# Game_Consol_Top.net
KiCad netlist of a schematic drawn in Altium Designer
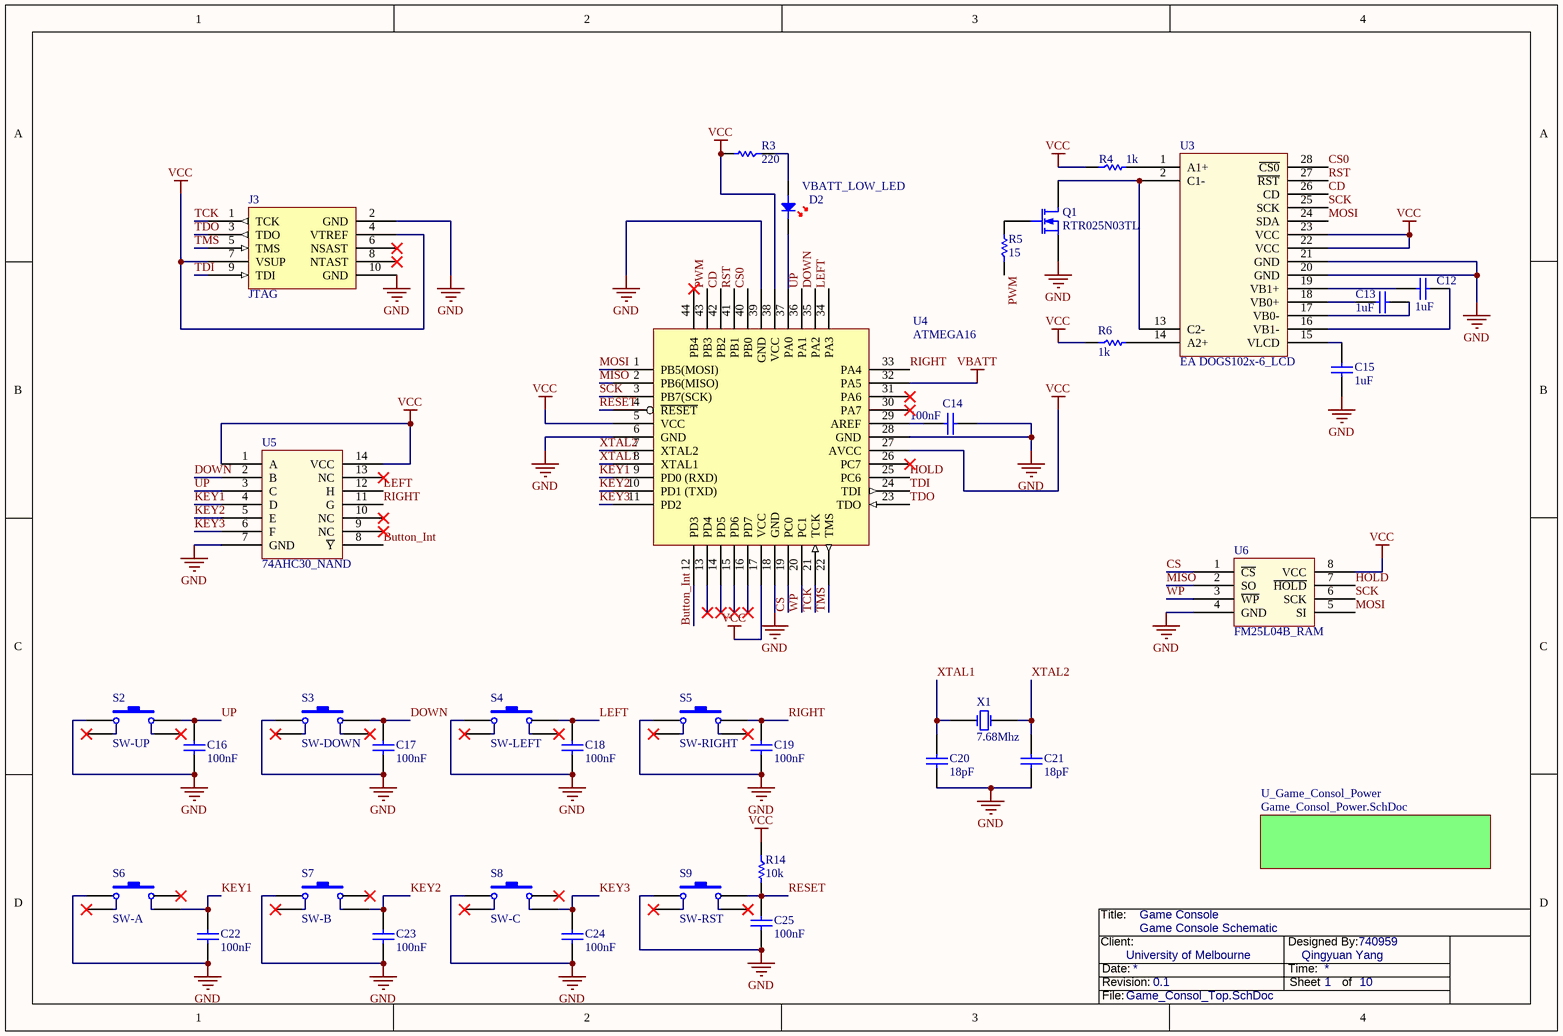
[diagram p0: Game_Consol_Top.SchDoc]

(export (version "E")
  (design (tool "Eeschema 10.0.6"))
  (components
    (comp (ref "C12")
      (value "1uF")
      (footprint "0805")
      (description "Capacitor 100nF")
      (libsource (lib "EmbSD Lib 0v1") (part "C 0805"))
    )
    (comp (ref "C13")
      (value "1uF")
      (footprint "0805")
      (description "Capacitor 100nF")
      (libsource (lib "EmbSD Lib 0v1") (part "C 0805"))
    )
    (comp (ref "C14")
      (value "100nF")
      (footprint "0805")
      (description "Capacitor 100nF")
      (libsource (lib "EmbSD Lib 0v1") (part "C 0805"))
    )
    (comp (ref "C15")
      (value "1uF")
      (footprint "0805")
      (description "Capacitor 100nF")
      (libsource (lib "EmbSD Lib 0v1") (part "C 0805"))
    )
    (comp (ref "C16")
      (value "100nF")
      (footprint "0805")
      (description "Capacitor 100nF")
      (libsource (lib "EmbSD Lib 0v1") (part "C 0805"))
    )
    (comp (ref "C17")
      (value "100nF")
      (footprint "0805")
      (description "Capacitor 100nF")
      (libsource (lib "EmbSD Lib 0v1") (part "C 0805"))
    )
    (comp (ref "C18")
      (value "100nF")
      (footprint "0805")
      (description "Capacitor 100nF")
      (libsource (lib "EmbSD Lib 0v1") (part "C 0805"))
    )
    (comp (ref "C19")
      (value "100nF")
      (footprint "0805")
      (description "Capacitor 100nF")
      (libsource (lib "EmbSD Lib 0v1") (part "C 0805"))
    )
    (comp (ref "C20")
      (value "18pF")
      (footprint "0805")
      (description "Capacitor 100nF")
      (libsource (lib "EmbSD Lib 0v1") (part "C 0805"))
    )
    (comp (ref "C21")
      (value "18pF")
      (footprint "0805")
      (description "Capacitor 100nF")
      (libsource (lib "EmbSD Lib 0v1") (part "C 0805"))
    )
    (comp (ref "C22")
      (value "100nF")
      (footprint "0805")
      (description "Capacitor 100nF")
      (libsource (lib "EmbSD Lib 0v1") (part "C 0805"))
    )
    (comp (ref "C23")
      (value "100nF")
      (footprint "0805")
      (description "Capacitor 100nF")
      (libsource (lib "EmbSD Lib 0v1") (part "C 0805"))
    )
    (comp (ref "C24")
      (value "100nF")
      (footprint "0805")
      (description "Capacitor 100nF")
      (libsource (lib "EmbSD Lib 0v1") (part "C 0805"))
    )
    (comp (ref "C25")
      (value "100nF")
      (footprint "0805")
      (description "Capacitor 100nF")
      (libsource (lib "EmbSD Lib 0v1") (part "C 0805"))
    )
    (comp (ref "D2")
      (value "VBATT_LOW_LED")
      (footprint "0805D")
      (description "Light Emitting Diode")
      (fields (field (name "MANUFACTURER") "Generic Components") (field (name "PUBLISHER") "Altium Limited"))
      (libsource (lib "EmbSD Lib 0v1") (part "LED RED"))
    )
    (comp (ref "J3")
      (value "JTAG")
      (footprint "BOXEDVERT10")
      (description "JTAG ATMEL connector")
      (libsource (lib "EmbSD Lib 0v1") (part "JTAG_CON"))
    )
    (comp (ref "Q1")
      (value "RTR025N03TL")
      (footprint "SOT23")
      (description "N-Channel MOSFET")
      (fields (field (name "PUBLISHER") "Altium Limited"))
      (libsource (lib "EmbSD Lib 0v1") (part "MOSFET-N"))
    )
    (comp (ref "R3")
      (value "220")
      (footprint "0805")
      (description "Resistor")
      (libsource (lib "EmbSD Lib 0v1") (part "R"))
    )
    (comp (ref "R4")
      (value "1k")
      (footprint "0805")
      (description "Resistor")
      (libsource (lib "EmbSD Lib 0v1") (part "R"))
    )
    (comp (ref "R5")
      (value "15")
      (footprint "0805")
      (description "Resistor")
      (libsource (lib "EmbSD Lib 0v1") (part "R"))
    )
    (comp (ref "R6")
      (value "1k")
      (footprint "0805")
      (description "Resistor")
      (libsource (lib "EmbSD Lib 0v1") (part "R"))
    )
    (comp (ref "R14")
      (value "10k")
      (footprint "0805")
      (description "Resistor")
      (libsource (lib "EmbSD Lib 0v1") (part "R"))
    )
    (comp (ref "S2")
      (value "SW-UP")
      (footprint "SPNO_SMD")
      (description "Push Button Switch")
      (fields
        (field (name "MANUFACTURER") "TE Connectivity")
        (field (name "MANUFACTURER PART NUMBER") "FSM4JSMA")
        (field (name "PUBLISHER") "Altium Limited")
      )
      (libsource (lib "EmbSD Lib 0v1") (part "SW-PB"))
    )
    (comp (ref "S3")
      (value "SW-DOWN")
      (footprint "SPNO_SMD")
      (description "Push Button Switch")
      (fields
        (field (name "MANUFACTURER") "TE Connectivity")
        (field (name "MANUFACTURER PART NUMBER") "FSM4JSMA")
        (field (name "PUBLISHER") "Altium Limited")
      )
      (libsource (lib "EmbSD Lib 0v1") (part "SW-PB"))
    )
    (comp (ref "S4")
      (value "SW-LEFT")
      (footprint "SPNO_SMD")
      (description "Push Button Switch")
      (fields
        (field (name "MANUFACTURER") "TE Connectivity")
        (field (name "MANUFACTURER PART NUMBER") "FSM4JSMA")
        (field (name "PUBLISHER") "Altium Limited")
      )
      (libsource (lib "EmbSD Lib 0v1") (part "SW-PB"))
    )
    (comp (ref "S5")
      (value "SW-RIGHT")
      (footprint "SPNO_SMD")
      (description "Push Button Switch")
      (fields
        (field (name "MANUFACTURER") "TE Connectivity")
        (field (name "MANUFACTURER PART NUMBER") "FSM4JSMA")
        (field (name "PUBLISHER") "Altium Limited")
      )
      (libsource (lib "EmbSD Lib 0v1") (part "SW-PB"))
    )
    (comp (ref "S6")
      (value "SW-A")
      (footprint "SPNO_SMD")
      (description "Push Button Switch")
      (fields
        (field (name "MANUFACTURER") "TE Connectivity")
        (field (name "MANUFACTURER PART NUMBER") "FSM4JSMA")
        (field (name "PUBLISHER") "Altium Limited")
      )
      (libsource (lib "EmbSD Lib 0v1") (part "SW-PB"))
    )
    (comp (ref "S7")
      (value "SW-B")
      (footprint "SPNO_SMD")
      (description "Push Button Switch")
      (fields
        (field (name "MANUFACTURER") "TE Connectivity")
        (field (name "MANUFACTURER PART NUMBER") "FSM4JSMA")
        (field (name "PUBLISHER") "Altium Limited")
      )
      (libsource (lib "EmbSD Lib 0v1") (part "SW-PB"))
    )
    (comp (ref "S8")
      (value "SW-C")
      (footprint "SPNO_SMD")
      (description "Push Button Switch")
      (fields
        (field (name "MANUFACTURER") "TE Connectivity")
        (field (name "MANUFACTURER PART NUMBER") "FSM4JSMA")
        (field (name "PUBLISHER") "Altium Limited")
      )
      (libsource (lib "EmbSD Lib 0v1") (part "SW-PB"))
    )
    (comp (ref "S9")
      (value "SW-RST")
      (footprint "SPNO_SMD")
      (description "Push Button Switch")
      (fields
        (field (name "MANUFACTURER") "TE Connectivity")
        (field (name "MANUFACTURER PART NUMBER") "FSM4JSMA")
        (field (name "PUBLISHER") "Altium Limited")
      )
      (libsource (lib "EmbSD Lib 0v1") (part "SW-PB"))
    )
    (comp (ref "U3")
      (value "EA DOGS102x-6_LCD")
      (footprint "EA DOGS102x")
      (description "LCD 102x64-pixel with backlight")
      (libsource (lib "EmbSD Lib 0v1") (part "EA DOGS102x-6"))
    )
    (comp (ref "U4")
      (value "ATMEGA16")
      (footprint "QFP-48")
      (description "ATMEGA16 Microcontroller")
      (libsource (lib "EmbSD Lib 0v1") (part "ATMEGA16"))
    )
    (comp (ref "U5")
      (value "74AHC30_NAND")
      (footprint "SOIC-14")
      (description "1 x 8 Input NAND gate")
      (libsource (lib "EmbSD Lib 0v1") (part "74AHC30"))
    )
    (comp (ref "U6")
      (value "FM25L04B_RAM")
      (footprint "SOIC-8")
      (description "FRAM 4Kb Memory")
      (libsource (lib "EmbSD Lib 0v1") (part "FM25L04B"))
    )
    (comp (ref "X1")
      (value "7.68Mhz")
      (footprint "XTAL_FLAT_SMD")
      (description "Crystal Oscillator")
      (libsource (lib "EmbSD Lib 0v1") (part "XTAL"))
    )
  )
  (nets
    (net (code "1") (name "/Button_Int") (class "Default")
      (node (ref "U4") (pin "12") (pinfunction "PD3_12") (pintype "passive"))
      (node (ref "U5") (pin "8") (pinfunction "~{Y}_8") (pintype "passive"))
    )
    (net (code "2") (name "/CD") (class "Default")
      (node (ref "U3") (pin "26") (pinfunction "CD_26") (pintype "passive"))
      (node (ref "U4") (pin "42") (pinfunction "PB2_42") (pintype "passive"))
    )
    (net (code "3") (name "/CS") (class "Default")
      (node (ref "U4") (pin "19") (pinfunction "PC0_19") (pintype "passive"))
      (node (ref "U6") (pin "1") (pinfunction "~{CS}_1") (pintype "passive"))
    )
    (net (code "4") (name "/CS0") (class "Default")
      (node (ref "U3") (pin "28") (pinfunction "~{CS0}_28") (pintype "passive"))
      (node (ref "U4") (pin "40") (pinfunction "PB0_40") (pintype "passive"))
    )
    (net (code "5") (name "/DOWN") (class "Default")
      (node (ref "C17") (pin "1") (pinfunction "1_1") (pintype "passive"))
      (node (ref "S3") (pin "3") (pinfunction "3_3") (pintype "passive"))
      (node (ref "U4") (pin "35") (pinfunction "PA2_35") (pintype "passive"))
      (node (ref "U5") (pin "2") (pinfunction "B_2") (pintype "passive"))
    )
    (net (code "6") (name "/HOLD") (class "Default")
      (node (ref "U4") (pin "25") (pinfunction "PC6_25") (pintype "passive"))
      (node (ref "U6") (pin "7") (pinfunction "~{HOLD}_7") (pintype "passive"))
    )
    (net (code "7") (name "/KEY1") (class "Default")
      (node (ref "C22") (pin "1") (pinfunction "1_1") (pintype "passive"))
      (node (ref "S6") (pin "4") (pinfunction "4_4") (pintype "passive"))
      (node (ref "U4") (pin "9") (pinfunction "PD0_(RXD)_9") (pintype "passive"))
      (node (ref "U5") (pin "4") (pinfunction "D_4") (pintype "passive"))
    )
    (net (code "8") (name "/KEY2") (class "Default")
      (node (ref "C23") (pin "1") (pinfunction "1_1") (pintype "passive"))
      (node (ref "S7") (pin "4") (pinfunction "4_4") (pintype "passive"))
      (node (ref "U4") (pin "10") (pinfunction "PD1_(TXD)_10") (pintype "passive"))
      (node (ref "U5") (pin "5") (pinfunction "E_5") (pintype "passive"))
    )
    (net (code "9") (name "/KEY3") (class "Default")
      (node (ref "C24") (pin "1") (pinfunction "1_1") (pintype "passive"))
      (node (ref "S8") (pin "4") (pinfunction "4_4") (pintype "passive"))
      (node (ref "U4") (pin "11") (pinfunction "PD2_11") (pintype "passive"))
      (node (ref "U5") (pin "6") (pinfunction "F_6") (pintype "passive"))
    )
    (net (code "10") (name "/LEFT") (class "Default")
      (node (ref "C18") (pin "1") (pinfunction "1_1") (pintype "passive"))
      (node (ref "S4") (pin "3") (pinfunction "3_3") (pintype "passive"))
      (node (ref "U4") (pin "34") (pinfunction "PA3_34") (pintype "passive"))
      (node (ref "U5") (pin "12") (pinfunction "H_12") (pintype "passive"))
    )
    (net (code "11") (name "/MISO") (class "Default")
      (node (ref "U4") (pin "2") (pinfunction "PB6(MISO)_2") (pintype "passive"))
      (node (ref "U6") (pin "2") (pinfunction "SO_2") (pintype "passive"))
    )
    (net (code "12") (name "/MOSI") (class "Default")
      (node (ref "U3") (pin "24") (pinfunction "SDA_24") (pintype "passive"))
      (node (ref "U4") (pin "1") (pinfunction "PB5(MOSI)_1") (pintype "passive"))
      (node (ref "U6") (pin "5") (pinfunction "SI_5") (pintype "passive"))
    )
    (net (code "13") (name "/PWM") (class "Default")
      (node (ref "R5") (pin "1") (pintype "passive"))
      (node (ref "U4") (pin "43") (pinfunction "PB3_43") (pintype "passive"))
    )
    (net (code "14") (name "/RESET") (class "Default")
      (node (ref "C25") (pin "1") (pinfunction "1_1") (pintype "passive"))
      (node (ref "R14") (pin "2") (pintype "passive"))
      (node (ref "S9") (pin "3") (pinfunction "3_3") (pintype "passive"))
      (node (ref "U4") (pin "4") (pinfunction "~{RESET}_4") (pintype "passive"))
    )
    (net (code "15") (name "/RIGHT") (class "Default")
      (node (ref "C19") (pin "1") (pinfunction "1_1") (pintype "passive"))
      (node (ref "S5") (pin "3") (pinfunction "3_3") (pintype "passive"))
      (node (ref "U4") (pin "33") (pinfunction "PA4_33") (pintype "passive"))
      (node (ref "U5") (pin "11") (pinfunction "G_11") (pintype "passive"))
    )
    (net (code "16") (name "/RST") (class "Default")
      (node (ref "U3") (pin "27") (pinfunction "~{RST}_27") (pintype "passive"))
      (node (ref "U4") (pin "41") (pinfunction "PB1_41") (pintype "passive"))
    )
    (net (code "17") (name "/SCK") (class "Default")
      (node (ref "U3") (pin "25") (pinfunction "SCK_25") (pintype "passive"))
      (node (ref "U4") (pin "3") (pinfunction "PB7(SCK)_3") (pintype "passive"))
      (node (ref "U6") (pin "6") (pinfunction "SCK_6") (pintype "passive"))
    )
    (net (code "18") (name "/TCK") (class "Default")
      (node (ref "J3") (pin "1") (pinfunction "TCK_1") (pintype "output"))
      (node (ref "U4") (pin "21") (pinfunction "TCK_21") (pintype "input"))
    )
    (net (code "19") (name "/TDI") (class "Default")
      (node (ref "J3") (pin "9") (pinfunction "TDI_9") (pintype "input"))
      (node (ref "U4") (pin "24") (pinfunction "TDI_24") (pintype "output"))
    )
    (net (code "20") (name "/TDO") (class "Default")
      (node (ref "J3") (pin "3") (pinfunction "TDO_3") (pintype "output"))
      (node (ref "U4") (pin "23") (pinfunction "TDO_23") (pintype "input"))
    )
    (net (code "21") (name "/TMS") (class "Default")
      (node (ref "J3") (pin "5") (pinfunction "TMS_5") (pintype "input"))
      (node (ref "U4") (pin "22") (pinfunction "TMS_22") (pintype "output"))
    )
    (net (code "22") (name "/UP") (class "Default")
      (node (ref "C16") (pin "1") (pinfunction "1_1") (pintype "passive"))
      (node (ref "S2") (pin "3") (pinfunction "3_3") (pintype "passive"))
      (node (ref "U4") (pin "36") (pinfunction "PA1_36") (pintype "passive"))
      (node (ref "U5") (pin "3") (pinfunction "C_3") (pintype "passive"))
    )
    (net (code "23") (name "/WP") (class "Default")
      (node (ref "U4") (pin "20") (pinfunction "PC1_20") (pintype "passive"))
      (node (ref "U6") (pin "3") (pinfunction "~{WP}_3") (pintype "passive"))
    )
    (net (code "24") (name "/XTAL1") (class "Default")
      (node (ref "C20") (pin "1") (pinfunction "1_1") (pintype "passive"))
      (node (ref "U4") (pin "8") (pinfunction "XTAL1_8") (pintype "passive"))
      (node (ref "X1") (pin "1") (pinfunction "OSC1_1") (pintype "passive"))
    )
    (net (code "25") (name "/XTAL2") (class "Default")
      (node (ref "C21") (pin "1") (pinfunction "1_1") (pintype "passive"))
      (node (ref "U4") (pin "7") (pinfunction "XTAL2_7") (pintype "passive"))
      (node (ref "X1") (pin "2") (pinfunction "OSC2_2") (pintype "passive"))
    )
    (net (code "26") (name "GND") (class "Default")
      (node (ref "C14") (pin "1") (pinfunction "1_1") (pintype "passive"))
      (node (ref "C15") (pin "2") (pinfunction "2_2") (pintype "passive"))
      (node (ref "C16") (pin "2") (pinfunction "2_2") (pintype "passive"))
      (node (ref "C17") (pin "2") (pinfunction "2_2") (pintype "passive"))
      (node (ref "C18") (pin "2") (pinfunction "2_2") (pintype "passive"))
      (node (ref "C19") (pin "2") (pinfunction "2_2") (pintype "passive"))
      (node (ref "C20") (pin "2") (pinfunction "2_2") (pintype "passive"))
      (node (ref "C21") (pin "2") (pinfunction "2_2") (pintype "passive"))
      (node (ref "C22") (pin "2") (pinfunction "2_2") (pintype "passive"))
      (node (ref "C23") (pin "2") (pinfunction "2_2") (pintype "passive"))
      (node (ref "C24") (pin "2") (pinfunction "2_2") (pintype "passive"))
      (node (ref "C25") (pin "2") (pinfunction "2_2") (pintype "passive"))
      (node (ref "J3") (pin "10") (pinfunction "GND_10") (pintype "passive"))
      (node (ref "J3") (pin "2") (pinfunction "GND_2") (pintype "passive"))
      (node (ref "Q1") (pin "2") (pinfunction "2_2") (pintype "passive"))
      (node (ref "S2") (pin "1") (pinfunction "1_1") (pintype "passive"))
      (node (ref "S3") (pin "1") (pinfunction "1_1") (pintype "passive"))
      (node (ref "S4") (pin "1") (pinfunction "1_1") (pintype "passive"))
      (node (ref "S5") (pin "1") (pinfunction "1_1") (pintype "passive"))
      (node (ref "S6") (pin "1") (pinfunction "1_1") (pintype "passive"))
      (node (ref "S7") (pin "1") (pinfunction "1_1") (pintype "passive"))
      (node (ref "S8") (pin "1") (pinfunction "1_1") (pintype "passive"))
      (node (ref "S9") (pin "1") (pinfunction "1_1") (pintype "passive"))
      (node (ref "U3") (pin "20") (pinfunction "GND_20") (pintype "passive"))
      (node (ref "U3") (pin "21") (pinfunction "GND_21") (pintype "passive"))
      (node (ref "U4") (pin "18") (pinfunction "GND_18") (pintype "passive"))
      (node (ref "U4") (pin "28") (pinfunction "GND_28") (pintype "passive"))
      (node (ref "U4") (pin "39") (pinfunction "GND_39") (pintype "passive"))
      (node (ref "U4") (pin "6") (pinfunction "GND_6") (pintype "passive"))
      (node (ref "U5") (pin "7") (pinfunction "GND_7") (pintype "passive"))
      (node (ref "U6") (pin "4") (pinfunction "GND_4") (pintype "passive"))
    )
    (net (code "27") (name "Net-(D2-PadA)") (class "Default")
      (node (ref "D2") (pin "A") (pinfunction "A_A") (pintype "passive"))
      (node (ref "R3") (pin "1") (pintype "passive"))
    )
    (net (code "28") (name "Net-(Q1-Pad1)") (class "Default")
      (node (ref "Q1") (pin "1") (pinfunction "1_1") (pintype "passive"))
      (node (ref "R5") (pin "2") (pintype "passive"))
    )
    (net (code "29") (name "Net-(U3-A1+)") (class "Default")
      (node (ref "R4") (pin "2") (pintype "passive"))
      (node (ref "U3") (pin "1") (pinfunction "A1+_1") (pintype "passive"))
    )
    (net (code "30") (name "Net-(U3-A2+)") (class "Default")
      (node (ref "R6") (pin "2") (pintype "passive"))
      (node (ref "U3") (pin "14") (pinfunction "A2+_14") (pintype "passive"))
    )
    (net (code "31") (name "Net-(U3-C1-)") (class "Default")
      (node (ref "Q1") (pin "3") (pinfunction "3_3") (pintype "passive"))
      (node (ref "U3") (pin "13") (pinfunction "C2-_13") (pintype "passive"))
      (node (ref "U3") (pin "2") (pinfunction "C1-_2") (pintype "passive"))
    )
    (net (code "32") (name "Net-(U3-VB0+)") (class "Default")
      (node (ref "C13") (pin "2") (pinfunction "2_2") (pintype "passive"))
      (node (ref "U3") (pin "18") (pinfunction "VB0+_18") (pintype "passive"))
    )
    (net (code "33") (name "Net-(U3-VB0-)") (class "Default")
      (node (ref "C13") (pin "1") (pinfunction "1_1") (pintype "passive"))
      (node (ref "U3") (pin "17") (pinfunction "VB0-_17") (pintype "passive"))
    )
    (net (code "34") (name "Net-(U3-VB1+)") (class "Default")
      (node (ref "C12") (pin "2") (pinfunction "2_2") (pintype "passive"))
      (node (ref "U3") (pin "19") (pinfunction "VB1+_19") (pintype "passive"))
    )
    (net (code "35") (name "Net-(U3-VB1-)") (class "Default")
      (node (ref "C12") (pin "1") (pinfunction "1_1") (pintype "passive"))
      (node (ref "U3") (pin "16") (pinfunction "VB1-_16") (pintype "passive"))
    )
    (net (code "36") (name "Net-(U3-VLCD)") (class "Default")
      (node (ref "C15") (pin "1") (pinfunction "1_1") (pintype "passive"))
      (node (ref "U3") (pin "15") (pinfunction "VLCD_15") (pintype "passive"))
    )
    (net (code "37") (name "Net-(U4-AREF)") (class "Default")
      (node (ref "C14") (pin "2") (pinfunction "2_2") (pintype "passive"))
      (node (ref "U4") (pin "29") (pinfunction "AREF_29") (pintype "passive"))
    )
    (net (code "38") (name "Net-(U4-PA0)") (class "Default")
      (node (ref "D2") (pin "K") (pinfunction "K_K") (pintype "passive"))
      (node (ref "U4") (pin "37") (pinfunction "PA0_37") (pintype "passive"))
    )
    (net (code "39") (name "VBATT") (class "Default")
      (node (ref "U4") (pin "32") (pinfunction "PA5_32") (pintype "passive"))
    )
    (net (code "40") (name "VCC") (class "Default")
      (node (ref "J3") (pin "4") (pinfunction "VTREF_4") (pintype "power_in"))
      (node (ref "J3") (pin "7") (pinfunction "VSUP_7") (pintype "passive"))
      (node (ref "R14") (pin "1") (pintype "passive"))
      (node (ref "R3") (pin "2") (pintype "passive"))
      (node (ref "R4") (pin "1") (pintype "passive"))
      (node (ref "R6") (pin "1") (pintype "passive"))
      (node (ref "U3") (pin "22") (pinfunction "VCC_22") (pintype "passive"))
      (node (ref "U3") (pin "23") (pinfunction "VCC_23") (pintype "passive"))
      (node (ref "U4") (pin "17") (pinfunction "VCC_17") (pintype "passive"))
      (node (ref "U4") (pin "27") (pinfunction "AVCC_27") (pintype "passive"))
      (node (ref "U4") (pin "38") (pinfunction "VCC_38") (pintype "passive"))
      (node (ref "U4") (pin "5") (pinfunction "VCC_5") (pintype "passive"))
      (node (ref "U5") (pin "1") (pinfunction "A_1") (pintype "passive"))
      (node (ref "U5") (pin "14") (pinfunction "VCC_14") (pintype "passive"))
      (node (ref "U6") (pin "8") (pinfunction "VCC_8") (pintype "passive"))
    )
    (net (code "41") (name "unconnected-(J3-NSAST-Pad6)") (class "Default")
      (node (ref "J3") (pin "6") (pinfunction "NSAST_6") (pintype "passive+no_connect"))
    )
    (net (code "42") (name "unconnected-(J3-NTAST-Pad8)") (class "Default")
      (node (ref "J3") (pin "8") (pinfunction "NTAST_8") (pintype "passive+no_connect"))
    )
    (net (code "43") (name "unconnected-(S2-Pad2)") (class "Default")
      (node (ref "S2") (pin "2") (pinfunction "2_2") (pintype "passive+no_connect"))
    )
    (net (code "44") (name "unconnected-(S2-Pad4)") (class "Default")
      (node (ref "S2") (pin "4") (pinfunction "4_4") (pintype "passive+no_connect"))
    )
    (net (code "45") (name "unconnected-(S3-Pad2)") (class "Default")
      (node (ref "S3") (pin "2") (pinfunction "2_2") (pintype "passive+no_connect"))
    )
    (net (code "46") (name "unconnected-(S3-Pad4)") (class "Default")
      (node (ref "S3") (pin "4") (pinfunction "4_4") (pintype "passive+no_connect"))
    )
    (net (code "47") (name "unconnected-(S4-Pad2)") (class "Default")
      (node (ref "S4") (pin "2") (pinfunction "2_2") (pintype "passive+no_connect"))
    )
    (net (code "48") (name "unconnected-(S4-Pad4)") (class "Default")
      (node (ref "S4") (pin "4") (pinfunction "4_4") (pintype "passive+no_connect"))
    )
    (net (code "49") (name "unconnected-(S5-Pad2)") (class "Default")
      (node (ref "S5") (pin "2") (pinfunction "2_2") (pintype "passive+no_connect"))
    )
    (net (code "50") (name "unconnected-(S5-Pad4)") (class "Default")
      (node (ref "S5") (pin "4") (pinfunction "4_4") (pintype "passive+no_connect"))
    )
    (net (code "51") (name "unconnected-(S6-Pad2)") (class "Default")
      (node (ref "S6") (pin "2") (pinfunction "2_2") (pintype "passive+no_connect"))
    )
    (net (code "52") (name "unconnected-(S6-Pad3)") (class "Default")
      (node (ref "S6") (pin "3") (pinfunction "3_3") (pintype "passive+no_connect"))
    )
    (net (code "53") (name "unconnected-(S7-Pad2)") (class "Default")
      (node (ref "S7") (pin "2") (pinfunction "2_2") (pintype "passive+no_connect"))
    )
    (net (code "54") (name "unconnected-(S7-Pad3)") (class "Default")
      (node (ref "S7") (pin "3") (pinfunction "3_3") (pintype "passive+no_connect"))
    )
    (net (code "55") (name "unconnected-(S8-Pad2)") (class "Default")
      (node (ref "S8") (pin "2") (pinfunction "2_2") (pintype "passive+no_connect"))
    )
    (net (code "56") (name "unconnected-(S8-Pad3)") (class "Default")
      (node (ref "S8") (pin "3") (pinfunction "3_3") (pintype "passive+no_connect"))
    )
    (net (code "57") (name "unconnected-(S9-Pad2)") (class "Default")
      (node (ref "S9") (pin "2") (pinfunction "2_2") (pintype "passive+no_connect"))
    )
    (net (code "58") (name "unconnected-(S9-Pad4)") (class "Default")
      (node (ref "S9") (pin "4") (pinfunction "4_4") (pintype "passive+no_connect"))
    )
    (net (code "59") (name "unconnected-(U3-Pad3)") (class "Default")
      (node (ref "U3") (pin "3") (pinfunction "3_3") (pintype "passive"))
    )
    (net (code "60") (name "unconnected-(U3-Pad4)") (class "Default")
      (node (ref "U3") (pin "4") (pinfunction "4_4") (pintype "passive"))
    )
    (net (code "61") (name "unconnected-(U3-Pad5)") (class "Default")
      (node (ref "U3") (pin "5") (pinfunction "5_5") (pintype "passive"))
    )
    (net (code "62") (name "unconnected-(U3-Pad6)") (class "Default")
      (node (ref "U3") (pin "6") (pinfunction "6_6") (pintype "passive"))
    )
    (net (code "63") (name "unconnected-(U3-Pad7)") (class "Default")
      (node (ref "U3") (pin "7") (pinfunction "7_7") (pintype "passive"))
    )
    (net (code "64") (name "unconnected-(U3-Pad8)") (class "Default")
      (node (ref "U3") (pin "8") (pinfunction "8_8") (pintype "passive"))
    )
    (net (code "65") (name "unconnected-(U3-Pad9)") (class "Default")
      (node (ref "U3") (pin "9") (pinfunction "9_9") (pintype "passive"))
    )
    (net (code "66") (name "unconnected-(U3-Pad10)") (class "Default")
      (node (ref "U3") (pin "10") (pinfunction "10_10") (pintype "passive"))
    )
    (net (code "67") (name "unconnected-(U3-Pad11)") (class "Default")
      (node (ref "U3") (pin "11") (pinfunction "11_11") (pintype "passive"))
    )
    (net (code "68") (name "unconnected-(U3-Pad12)") (class "Default")
      (node (ref "U3") (pin "12") (pinfunction "12_12") (pintype "passive"))
    )
    (net (code "69") (name "unconnected-(U4-PA6-Pad31)") (class "Default")
      (node (ref "U4") (pin "31") (pinfunction "PA6_31") (pintype "passive+no_connect"))
    )
    (net (code "70") (name "unconnected-(U4-PA7-Pad30)") (class "Default")
      (node (ref "U4") (pin "30") (pinfunction "PA7_30") (pintype "passive+no_connect"))
    )
    (net (code "71") (name "unconnected-(U4-PB4-Pad44)") (class "Default")
      (node (ref "U4") (pin "44") (pinfunction "PB4_44") (pintype "passive+no_connect"))
    )
    (net (code "72") (name "unconnected-(U4-PC7-Pad26)") (class "Default")
      (node (ref "U4") (pin "26") (pinfunction "PC7_26") (pintype "passive+no_connect"))
    )
    (net (code "73") (name "unconnected-(U4-PD4-Pad13)") (class "Default")
      (node (ref "U4") (pin "13") (pinfunction "PD4_13") (pintype "passive+no_connect"))
    )
    (net (code "74") (name "unconnected-(U4-PD5-Pad14)") (class "Default")
      (node (ref "U4") (pin "14") (pinfunction "PD5_14") (pintype "passive+no_connect"))
    )
    (net (code "75") (name "unconnected-(U4-PD6-Pad15)") (class "Default")
      (node (ref "U4") (pin "15") (pinfunction "PD6_15") (pintype "passive+no_connect"))
    )
    (net (code "76") (name "unconnected-(U4-PD7-Pad16)") (class "Default")
      (node (ref "U4") (pin "16") (pinfunction "PD7_16") (pintype "passive+no_connect"))
    )
    (net (code "77") (name "unconnected-(U5-NC-Pad9)") (class "Default")
      (node (ref "U5") (pin "9") (pinfunction "NC_9") (pintype "passive+no_connect"))
    )
    (net (code "78") (name "unconnected-(U5-NC-Pad10)") (class "Default")
      (node (ref "U5") (pin "10") (pinfunction "NC_10") (pintype "passive+no_connect"))
    )
    (net (code "79") (name "unconnected-(U5-NC-Pad13)") (class "Default")
      (node (ref "U5") (pin "13") (pinfunction "NC_13") (pintype "passive+no_connect"))
    )
  )
)
